# tracker.net
KiCad netlist of a schematic drawn in EAGLE
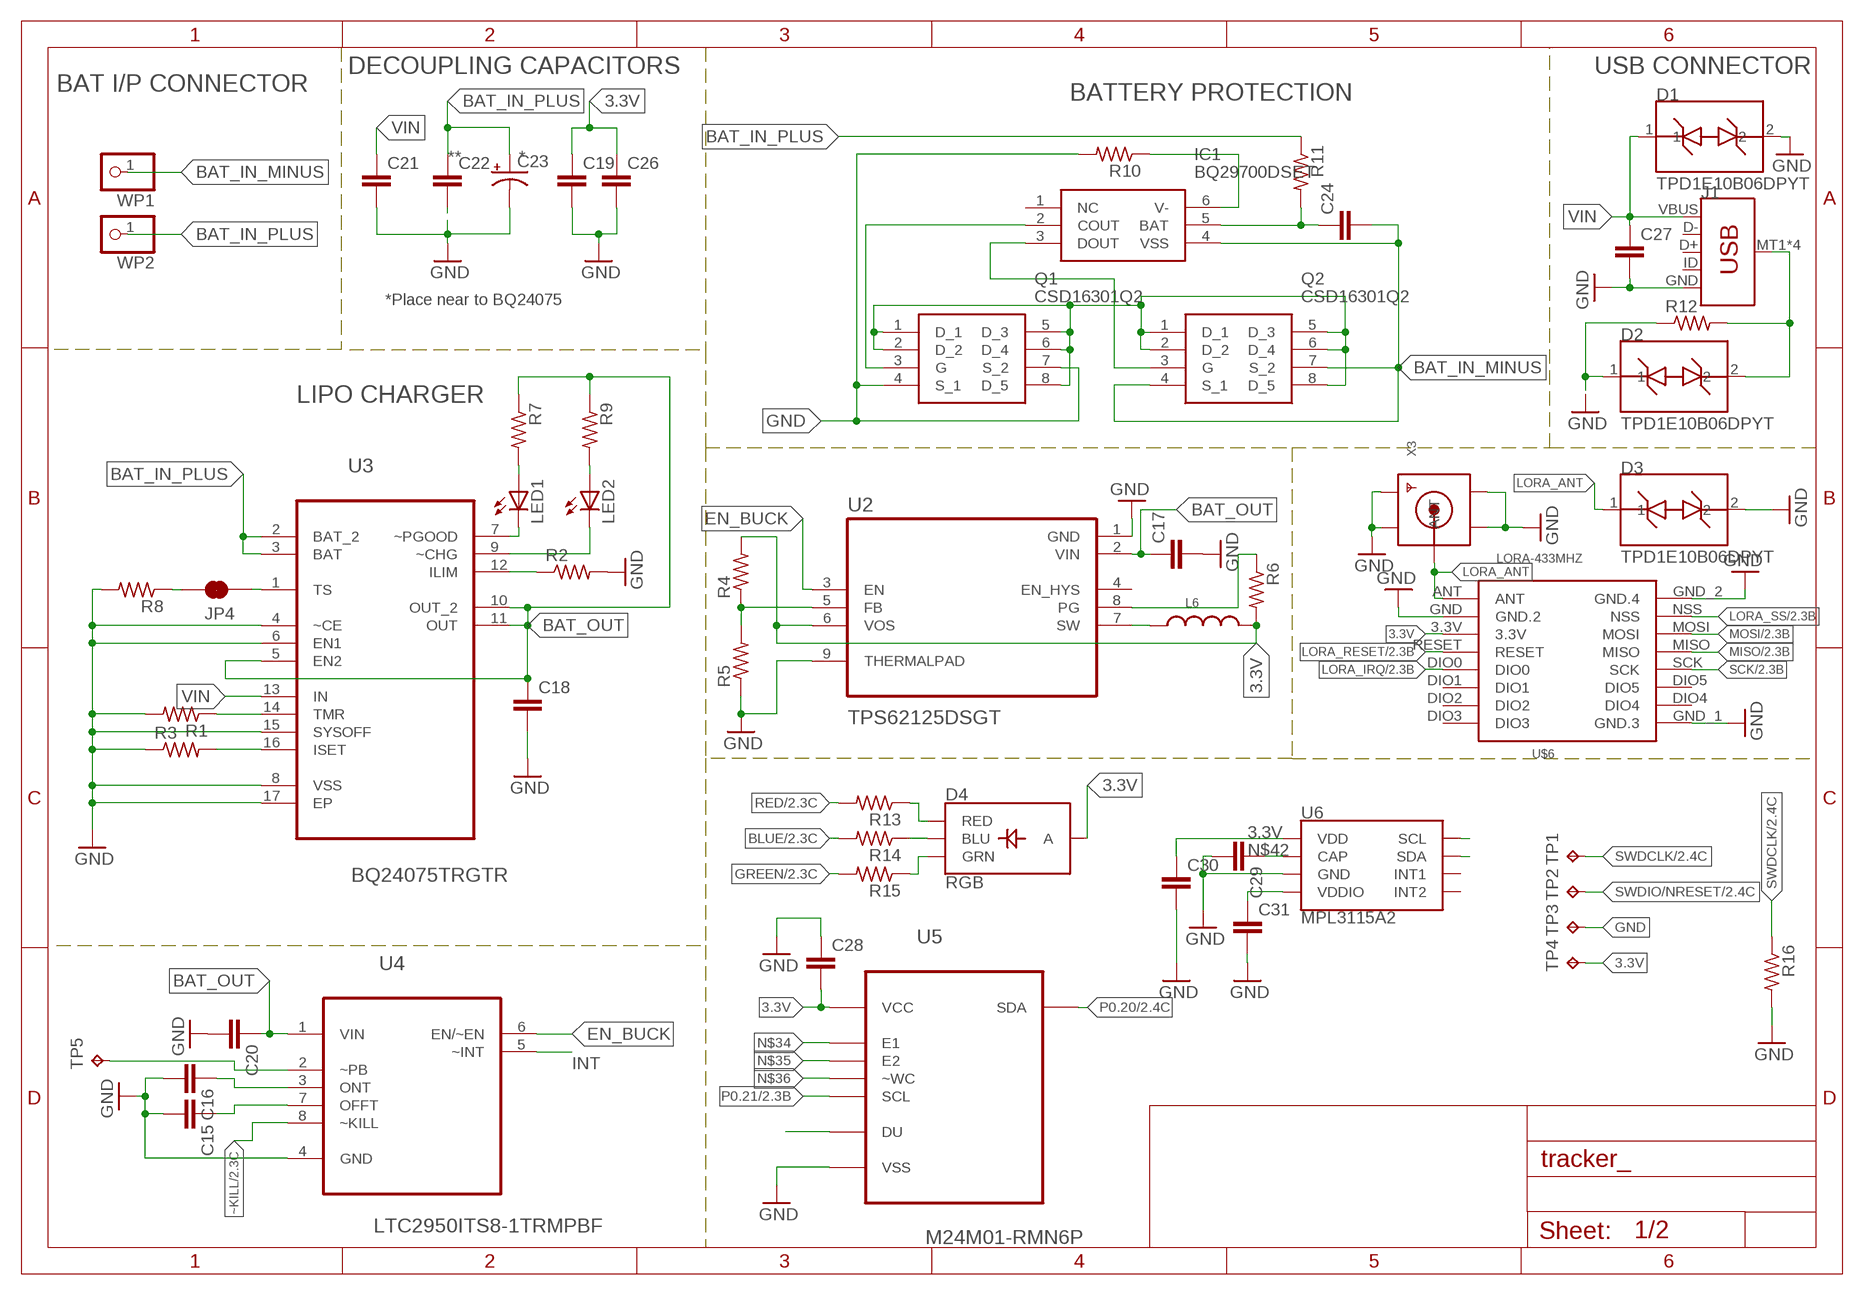
[diagram p0: schematic, sheet 1]
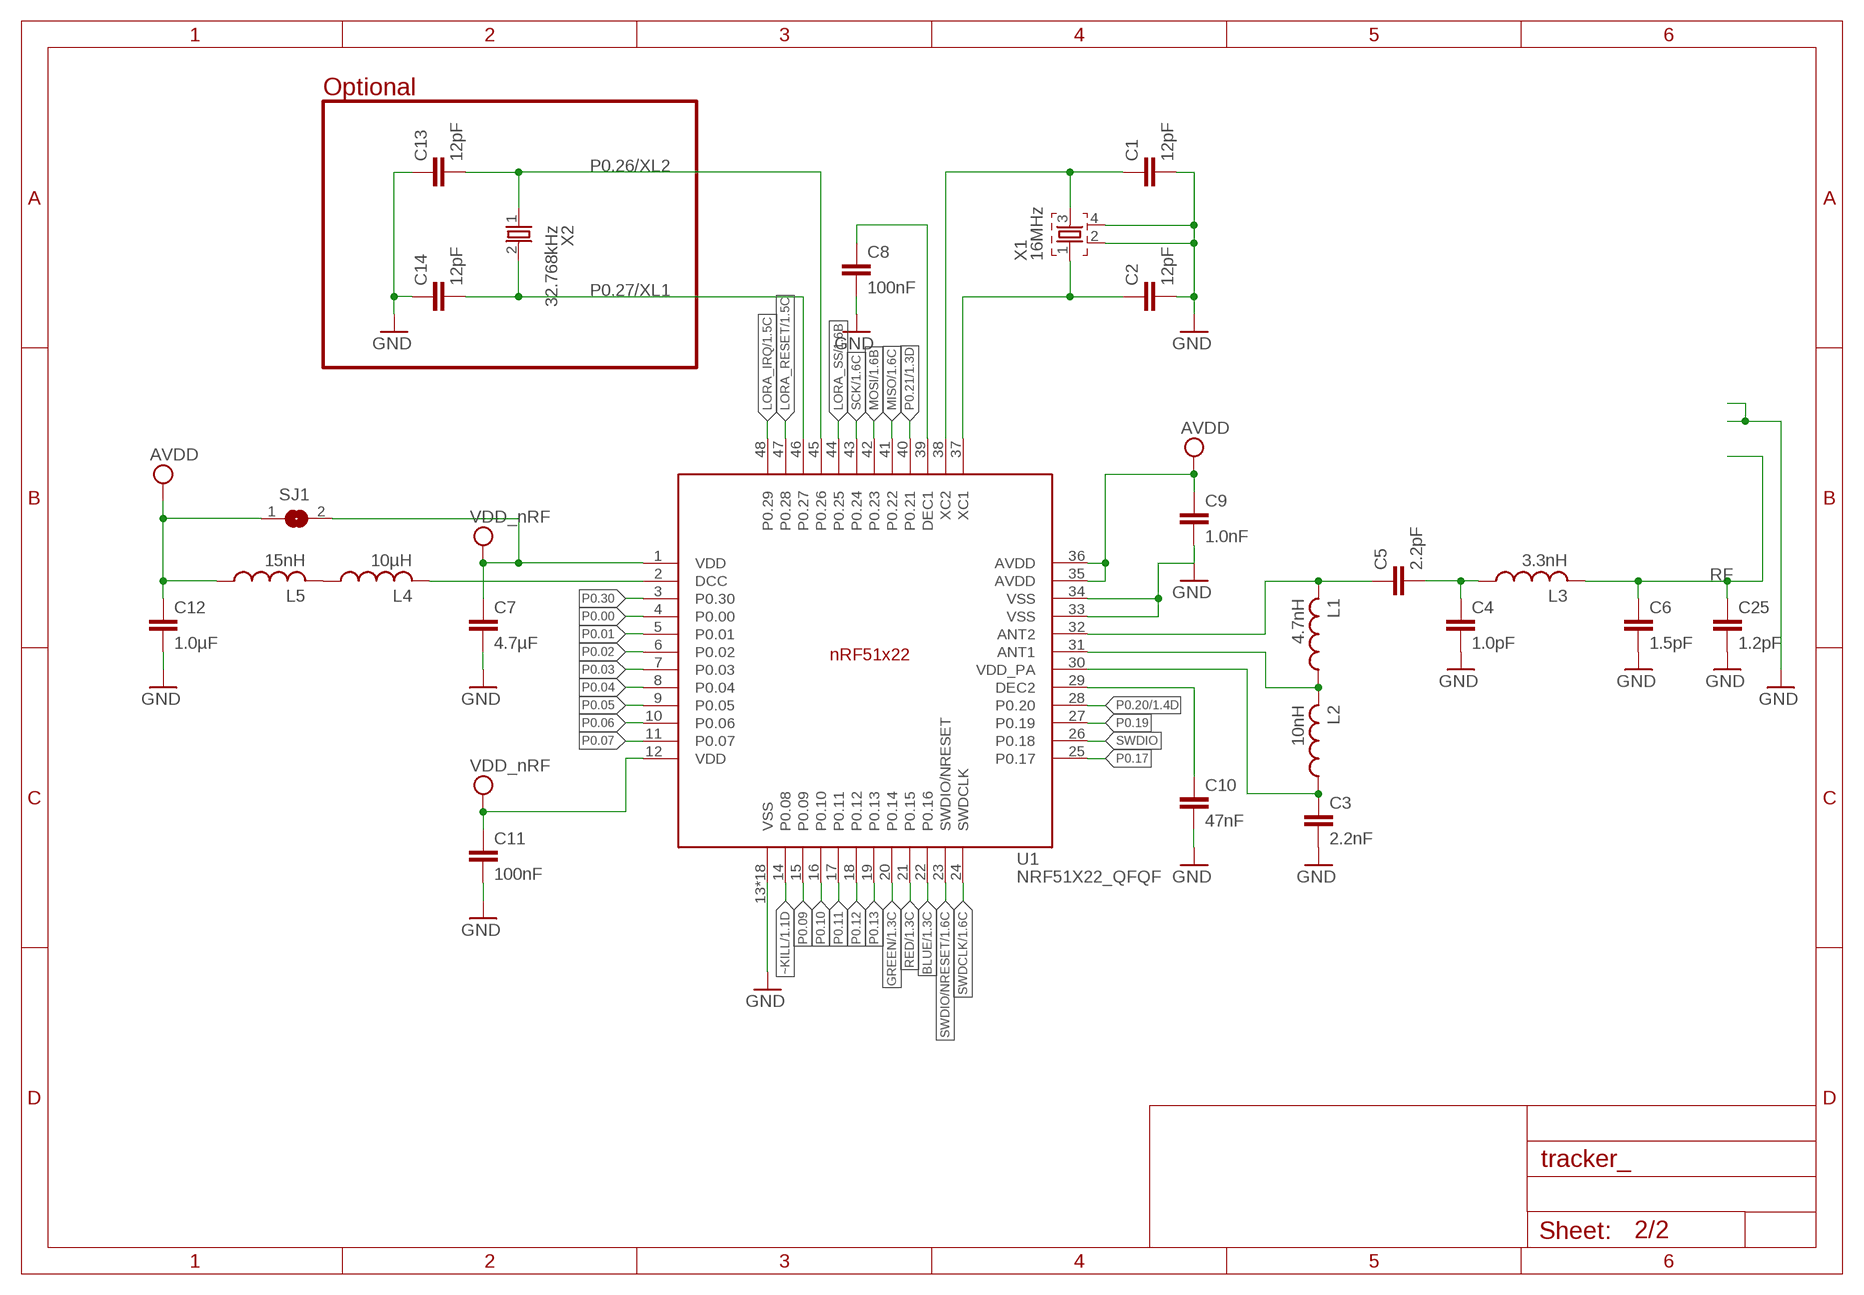
[diagram p1: schematic, sheet 2]

(export (version "E")
  (design (tool "Eeschema 10.0.6"))
  (components
    (comp (ref "C1")
      (value "12pF")
      (footprint "eagle-import:RESC0402_N")
      (libsource (lib "eagle-import") (part "CAPACITOR_0402_N"))
    )
    (comp (ref "C2")
      (value "12pF")
      (footprint "eagle-import:RESC0402_N")
      (libsource (lib "eagle-import") (part "CAPACITOR_0402_N"))
    )
    (comp (ref "C3")
      (value "2.2nF")
      (footprint "eagle-import:RESC0402_N")
      (libsource (lib "eagle-import") (part "CAPACITOR_0402_N"))
    )
    (comp (ref "C4")
      (value "1.0pF")
      (footprint "eagle-import:RESC0402_N")
      (libsource (lib "eagle-import") (part "CAPACITOR_0402_N"))
    )
    (comp (ref "C5")
      (value "2.2pF")
      (footprint "eagle-import:RESC0402_N")
      (libsource (lib "eagle-import") (part "CAPACITOR_0402_N"))
    )
    (comp (ref "C6")
      (value "1.5pF")
      (footprint "eagle-import:RESC0402_N")
      (libsource (lib "eagle-import") (part "CAPACITOR_0402_N"))
    )
    (comp (ref "C7")
      (value "4.7µF")
      (footprint "eagle-import:RESC0603_N")
      (libsource (lib "eagle-import") (part "CAPACITOR_0603_N"))
    )
    (comp (ref "C8")
      (value "100nF")
      (footprint "eagle-import:RESC0402_N")
      (libsource (lib "eagle-import") (part "CAPACITOR_0402_N"))
    )
    (comp (ref "C9")
      (value "1.0nF")
      (footprint "eagle-import:RESC0402_N")
      (libsource (lib "eagle-import") (part "CAPACITOR_0402_N"))
    )
    (comp (ref "C10")
      (value "47nF")
      (footprint "eagle-import:RESC0402_N")
      (libsource (lib "eagle-import") (part "CAPACITOR_0402_N"))
    )
    (comp (ref "C11")
      (value "100nF")
      (footprint "eagle-import:RESC0402_N")
      (libsource (lib "eagle-import") (part "CAPACITOR_0402_N"))
    )
    (comp (ref "C12")
      (value "1.0µF")
      (footprint "eagle-import:RESC0603_N")
      (libsource (lib "eagle-import") (part "CAPACITOR_0603_N"))
    )
    (comp (ref "C13")
      (value "12pF")
      (footprint "eagle-import:RESC0402_N")
      (libsource (lib "eagle-import") (part "CAPACITOR_0402_N"))
    )
    (comp (ref "C14")
      (value "12pF")
      (footprint "eagle-import:RESC0402_N")
      (libsource (lib "eagle-import") (part "CAPACITOR_0402_N"))
    )
    (comp (ref "C25")
      (value "1.2pF")
      (footprint "eagle-import:RESC0402_N")
      (libsource (lib "eagle-import") (part "CAPACITOR_0402_N"))
    )
    (comp (ref "L1")
      (value "4.7nH")
      (footprint "eagle-import:RESC0402_N")
      (libsource (lib "eagle-import") (part "INDUCTOR_0402_N"))
    )
    (comp (ref "L2")
      (value "10nH")
      (footprint "eagle-import:RESC0402_N")
      (libsource (lib "eagle-import") (part "INDUCTOR_0402_N"))
    )
    (comp (ref "L3")
      (value "3.3nH")
      (footprint "eagle-import:RESC0402_N")
      (libsource (lib "eagle-import") (part "INDUCTOR_0402_N"))
    )
    (comp (ref "L4")
      (value "10µH")
      (footprint "eagle-import:RESC0603_N")
      (libsource (lib "eagle-import") (part "INDUCTOR_0603_N"))
    )
    (comp (ref "L5")
      (value "15nH")
      (footprint "eagle-import:RESC0402_N")
      (libsource (lib "eagle-import") (part "INDUCTOR_0402_N"))
    )
    (comp (ref "SJ1") (value "SJ") (footprint "eagle-import:SJ") (libsource (lib "eagle-import") (part "SJ")))
    (comp (ref "U1")
      (value "NRF51X22_QFQF")
      (footprint "eagle-import:QFN40P600X600X90-48_N")
      (libsource (lib "eagle-import") (part "NRF51X22_QFQF"))
    )
    (comp (ref "X1")
      (value "16MHz")
      (footprint "eagle-import:BT-XTAL_2016_N")
      (libsource (lib "eagle-import") (part "XTAL_32MHZ"))
    )
    (comp (ref "X2")
      (value "32.768kHz")
      (footprint "eagle-import:XTAL_3215_N")
      (libsource (lib "eagle-import") (part "XTAL_32KHZ"))
    )
    (comp (ref "C15")
      (value "C-EUC0402")
      (footprint "eagle-import:C0402")
      (libsource (lib "eagle-import") (part "C-EUC0402"))
    )
    (comp (ref "C16")
      (value "C-EUC0402")
      (footprint "eagle-import:C0402")
      (libsource (lib "eagle-import") (part "C-EUC0402"))
    )
    (comp (ref "C17")
      (value "C-EUC0402")
      (footprint "eagle-import:C0402")
      (libsource (lib "eagle-import") (part "C-EUC0402"))
    )
    (comp (ref "C18")
      (value "C-EUC0402")
      (footprint "eagle-import:C0402")
      (libsource (lib "eagle-import") (part "C-EUC0402"))
    )
    (comp (ref "C19")
      (value "C-EUC0603")
      (footprint "eagle-import:C0603")
      (libsource (lib "eagle-import") (part "C-EUC0603"))
    )
    (comp (ref "C20")
      (value "C-EUC0402")
      (footprint "eagle-import:C0402")
      (libsource (lib "eagle-import") (part "C-EUC0402"))
    )
    (comp (ref "C21")
      (value "C-EUC0402")
      (footprint "eagle-import:C0402")
      (libsource (lib "eagle-import") (part "C-EUC0402"))
    )
    (comp (ref "C22")
      (value "C-EUC0805K")
      (footprint "eagle-import:C0805K")
      (libsource (lib "eagle-import") (part "C-EUC0805K"))
    )
    (comp (ref "C23")
      (value "CPOL-USB/3528-21W")
      (footprint "eagle-import:B_3528-21W")
      (libsource (lib "eagle-import") (part "CPOL-USB/3528-21W"))
    )
    (comp (ref "C24")
      (value "C-EUC0603")
      (footprint "eagle-import:C0603")
      (libsource (lib "eagle-import") (part "C-EUC0603"))
    )
    (comp (ref "C26")
      (value "C-EUC0603")
      (footprint "eagle-import:C0603")
      (libsource (lib "eagle-import") (part "C-EUC0603"))
    )
    (comp (ref "C27")
      (value "C-EUC0603")
      (footprint "eagle-import:C0603")
      (libsource (lib "eagle-import") (part "C-EUC0603"))
    )
    (comp (ref "C28")
      (value "C-EUC0402")
      (footprint "eagle-import:C0402")
      (libsource (lib "eagle-import") (part "C-EUC0402"))
    )
    (comp (ref "C29")
      (value "C-EUC0402")
      (footprint "eagle-import:C0402")
      (libsource (lib "eagle-import") (part "C-EUC0402"))
    )
    (comp (ref "C30")
      (value "C-EUC0402")
      (footprint "eagle-import:C0402")
      (libsource (lib "eagle-import") (part "C-EUC0402"))
    )
    (comp (ref "C31")
      (value "C-EUC0402")
      (footprint "eagle-import:C0402")
      (libsource (lib "eagle-import") (part "C-EUC0402"))
    )
    (comp (ref "D1")
      (value "TPD1E10B06DPYT")
      (footprint "eagle-import:DFN100X60X45-2N")
      (fields (field (name "MF") "Texas Instruments"))
      (libsource (lib "eagle-import") (part "TPD1E10B06DPYT"))
    )
    (comp (ref "D2")
      (value "TPD1E10B06DPYT")
      (footprint "eagle-import:DFN100X60X45-2N")
      (fields (field (name "MF") "Texas Instruments"))
      (libsource (lib "eagle-import") (part "TPD1E10B06DPYT"))
    )
    (comp (ref "D3")
      (value "TPD1E10B06DPYT")
      (footprint "eagle-import:DFN100X60X45-2N")
      (fields (field (name "MF") "Texas Instruments"))
      (libsource (lib "eagle-import") (part "TPD1E10B06DPYT"))
    )
    (comp (ref "D4")
      (value "RGB")
      (footprint "eagle-import:P-LCC-4-3")
      (libsource (lib "eagle-import") (part "LED-RGB-CAPLCC"))
    )
    (comp (ref "IC1")
      (value "BQ29700DSET")
      (footprint "eagle-import:SON50P150X150X80-6N")
      (fields (field (name "RS_PART_NUMBER") "1456841"))
      (libsource (lib "eagle-import") (part "BQ29700DSET"))
    )
    (comp (ref "J1")
      (value "USB_MICRO-B_SMT")
      (footprint "eagle-import:USB-MICROB")
      (libsource (lib "eagle-import") (part "USB_MICRO-B_SMT"))
    )
    (comp (ref "JP4")
      (value "JUMPER-SMT_2_NC_TRACE_SILK")
      (footprint "eagle-import:SMT-JUMPER_2_NC_TRACE_SILK")
      (libsource (lib "eagle-import") (part "JUMPER-SMT_2_NC_TRACE_SILK"))
    )
    (comp (ref "L6")
      (value "WE-GF_1210(M)_744764115")
      (footprint "eagle-import:WE-GF_1210")
      (libsource (lib "eagle-import") (part "WE-GF_1210(M)_744764115"))
    )
    (comp (ref "LED1")
      (value "LEDCHIPLED_0603")
      (footprint "eagle-import:CHIPLED_0603")
      (libsource (lib "eagle-import") (part "LEDCHIPLED_0603"))
    )
    (comp (ref "LED2")
      (value "LEDCHIPLED_0603")
      (footprint "eagle-import:CHIPLED_0603")
      (libsource (lib "eagle-import") (part "LEDCHIPLED_0603"))
    )
    (comp (ref "Q1")
      (value "CSD16301Q2")
      (footprint "eagle-import:CSD16301Q2")
      (fields (field (name "RS_PART_NUMBER") "1628525"))
      (libsource (lib "eagle-import") (part "CSD16301Q2"))
    )
    (comp (ref "Q2")
      (value "CSD16301Q2")
      (footprint "eagle-import:CSD16301Q2")
      (fields (field (name "RS_PART_NUMBER") "1628525"))
      (libsource (lib "eagle-import") (part "CSD16301Q2"))
    )
    (comp (ref "R1")
      (value "R-US_R0402")
      (footprint "eagle-import:R0402")
      (libsource (lib "eagle-import") (part "R-US_R0402"))
    )
    (comp (ref "R2")
      (value "R-US_R0402")
      (footprint "eagle-import:R0402")
      (libsource (lib "eagle-import") (part "R-US_R0402"))
    )
    (comp (ref "R3")
      (value "R-US_R0402")
      (footprint "eagle-import:R0402")
      (libsource (lib "eagle-import") (part "R-US_R0402"))
    )
    (comp (ref "R4")
      (value "R-US_R0402")
      (footprint "eagle-import:R0402")
      (libsource (lib "eagle-import") (part "R-US_R0402"))
    )
    (comp (ref "R5")
      (value "R-US_R0402")
      (footprint "eagle-import:R0402")
      (libsource (lib "eagle-import") (part "R-US_R0402"))
    )
    (comp (ref "R6")
      (value "R-US_R0402")
      (footprint "eagle-import:R0402")
      (libsource (lib "eagle-import") (part "R-US_R0402"))
    )
    (comp (ref "R7")
      (value "R-US_R0402")
      (footprint "eagle-import:R0402")
      (libsource (lib "eagle-import") (part "R-US_R0402"))
    )
    (comp (ref "R8")
      (value "R-US_R0402")
      (footprint "eagle-import:R0402")
      (libsource (lib "eagle-import") (part "R-US_R0402"))
    )
    (comp (ref "R9")
      (value "R-US_R0402")
      (footprint "eagle-import:R0402")
      (libsource (lib "eagle-import") (part "R-US_R0402"))
    )
    (comp (ref "R10")
      (value "R-US_R0402")
      (footprint "eagle-import:R0402")
      (libsource (lib "eagle-import") (part "R-US_R0402"))
    )
    (comp (ref "R11")
      (value "R-US_M0805")
      (footprint "eagle-import:M0805")
      (libsource (lib "eagle-import") (part "R-US_M0805"))
    )
    (comp (ref "R12")
      (value "R-US_R0402")
      (footprint "eagle-import:R0402")
      (libsource (lib "eagle-import") (part "R-US_R0402"))
    )
    (comp (ref "R13")
      (value "R-US_R0402")
      (footprint "eagle-import:R0402")
      (libsource (lib "eagle-import") (part "R-US_R0402"))
    )
    (comp (ref "R14")
      (value "R-US_R0402")
      (footprint "eagle-import:R0402")
      (libsource (lib "eagle-import") (part "R-US_R0402"))
    )
    (comp (ref "R15")
      (value "R-US_R0402")
      (footprint "eagle-import:R0402")
      (libsource (lib "eagle-import") (part "R-US_R0402"))
    )
    (comp (ref "R16")
      (value "R-US_R0402")
      (footprint "eagle-import:R0402")
      (libsource (lib "eagle-import") (part "R-US_R0402"))
    )
    (comp (ref "TP1")
      (value "TPB1,27")
      (footprint "eagle-import:B1,27")
      (libsource (lib "eagle-import") (part "TPB1,27"))
    )
    (comp (ref "TP2")
      (value "TPB1,27")
      (footprint "eagle-import:B1,27")
      (libsource (lib "eagle-import") (part "TPB1,27"))
    )
    (comp (ref "TP3")
      (value "TPB1,27")
      (footprint "eagle-import:B1,27")
      (libsource (lib "eagle-import") (part "TPB1,27"))
    )
    (comp (ref "TP4")
      (value "TPB1,27")
      (footprint "eagle-import:B1,27")
      (libsource (lib "eagle-import") (part "TPB1,27"))
    )
    (comp (ref "TP5")
      (value "TPB1,27")
      (footprint "eagle-import:B1,27")
      (libsource (lib "eagle-import") (part "TPB1,27"))
    )
    (comp (ref "U$6")
      (value "LORA-433MHZ")
      (footprint "eagle-import:LORA-RA1-SMD")
      (libsource (lib "eagle-import") (part "LORA-RA-01-433MHZ"))
    )
    (comp (ref "U2")
      (value "TPS62125DSGT")
      (footprint "eagle-import:SON50P200X200X80-9N")
      (fields (field (name "MF") "Texas Instruments"))
      (libsource (lib "eagle-import") (part "TPS62125DSGT"))
    )
    (comp (ref "U3")
      (value "BQ24075TRGTR")
      (footprint "eagle-import:QFN50P300X300X100-17N")
      (libsource (lib "eagle-import") (part "BQ24075TRGTR"))
    )
    (comp (ref "U4")
      (value "LTC2950ITS8-1TRMPBF")
      (footprint "eagle-import:SOT65P280X100-8N")
      (fields (field (name "MPN") "LTC2950ITS8-1#TRMPBF"))
      (libsource (lib "eagle-import") (part "LTC2950ITS8-1TRMPBF"))
    )
    (comp (ref "U5")
      (value "M24M01-RMN6P")
      (footprint "eagle-import:SOIC127P600X175-8N")
      (libsource (lib "eagle-import") (part "M24M01-RMN6P"))
    )
    (comp (ref "U6")
      (value "MPL3115A2")
      (footprint "eagle-import:LGA-8-5X3")
      (libsource (lib "eagle-import") (part "MPL3115A2"))
    )
    (comp (ref "WP1")
      (value "WPAD-1-0805")
      (footprint "eagle-import:WPAD-1-0805")
      (libsource (lib "eagle-import") (part "WPAD-1-0805"))
    )
    (comp (ref "WP2")
      (value "WPAD-1-0805")
      (footprint "eagle-import:WPAD-1-0805")
      (libsource (lib "eagle-import") (part "WPAD-1-0805"))
    )
    (comp (ref "X3")
      (value "SMACONNECTOR_EDGE")
      (footprint "eagle-import:SMA_EDGELAUNCH")
      (libsource (lib "eagle-import") (part "SMACONNECTOR_EDGE"))
    )
  )
  (nets
    (net (code "1") (name "3.3V") (class "Default")
      (node (ref "C11") (pin "1") (pinfunction "1_1") (pintype "passive"))
      (node (ref "C19") (pin "1") (pinfunction "1_1") (pintype "passive"))
      (node (ref "C26") (pin "1") (pinfunction "1_1") (pintype "passive"))
      (node (ref "C28") (pin "2") (pinfunction "2_2") (pintype "passive"))
      (node (ref "C30") (pin "1") (pinfunction "1_1") (pintype "passive"))
      (node (ref "C7") (pin "1") (pinfunction "1_1") (pintype "passive"))
      (node (ref "D4") (pin "4") (pinfunction "A_4") (pintype "bidirectional"))
      (node (ref "L6") (pin "2") (pinfunction "2_2") (pintype "passive"))
      (node (ref "R4") (pin "2") (pinfunction "2_2") (pintype "passive"))
      (node (ref "R6") (pin "2") (pinfunction "2_2") (pintype "passive"))
      (node (ref "SJ1") (pin "2") (pinfunction "2_2") (pintype "passive"))
      (node (ref "TP4") (pin "TP") (pinfunction "TP_TP") (pintype "input"))
      (node (ref "U$6") (pin "3.3V") (pinfunction "3.3V_3.3V") (pintype "power_in"))
      (node (ref "U1") (pin "1") (pinfunction "VDD_1") (pintype "power_in"))
      (node (ref "U1") (pin "12") (pinfunction "VDD_12") (pintype "power_in"))
      (node (ref "U2") (pin "6") (pinfunction "VOS_6") (pintype "input"))
      (node (ref "U5") (pin "8") (pinfunction "VCC_8") (pintype "power_in"))
      (node (ref "U6") (pin "1") (pinfunction "VDD_1") (pintype "power_in"))
    )
    (net (code "2") (name "AVDD") (class "Default")
      (node (ref "C12") (pin "1") (pinfunction "1_1") (pintype "passive"))
      (node (ref "C9") (pin "1") (pinfunction "1_1") (pintype "passive"))
      (node (ref "L5") (pin "1") (pinfunction "1_1") (pintype "passive"))
      (node (ref "SJ1") (pin "1") (pinfunction "1_1") (pintype "passive"))
      (node (ref "U1") (pin "35") (pinfunction "AVDD_35") (pintype "power_in"))
      (node (ref "U1") (pin "36") (pinfunction "AVDD_36") (pintype "power_in"))
    )
    (net (code "3") (name "BAT_IN_MINUS") (class "Default")
      (node (ref "C24") (pin "2") (pinfunction "2_2") (pintype "passive"))
      (node (ref "IC1") (pin "4") (pinfunction "VSS_4") (pintype "power_in"))
      (node (ref "Q2") (pin "4") (pinfunction "S_1_4") (pintype "bidirectional"))
      (node (ref "Q2") (pin "7") (pinfunction "S_2_7") (pintype "bidirectional"))
      (node (ref "WP1") (pin "1") (pinfunction "1_1") (pintype "passive"))
    )
    (net (code "4") (name "BAT_IN_PLUS") (class "Default")
      (node (ref "C22") (pin "1") (pinfunction "1_1") (pintype "passive"))
      (node (ref "C23") (pin "+") (pinfunction "+_+") (pintype "passive"))
      (node (ref "R11") (pin "1") (pinfunction "1_1") (pintype "passive"))
      (node (ref "U3") (pin "2") (pinfunction "BAT_2_2") (pintype "bidirectional"))
      (node (ref "U3") (pin "3") (pinfunction "BAT_3") (pintype "bidirectional"))
      (node (ref "WP2") (pin "1") (pinfunction "1_1") (pintype "passive"))
    )
    (net (code "5") (name "BAT_OUT") (class "Default")
      (node (ref "C17") (pin "1") (pinfunction "1_1") (pintype "passive"))
      (node (ref "C18") (pin "1") (pinfunction "1_1") (pintype "passive"))
      (node (ref "C20") (pin "1") (pinfunction "1_1") (pintype "passive"))
      (node (ref "R7") (pin "1") (pinfunction "1_1") (pintype "passive"))
      (node (ref "R9") (pin "1") (pinfunction "1_1") (pintype "passive"))
      (node (ref "U2") (pin "2") (pinfunction "VIN_2") (pintype "power_in"))
      (node (ref "U3") (pin "10") (pinfunction "OUT_2_10") (pintype "output"))
      (node (ref "U3") (pin "11") (pinfunction "OUT_11") (pintype "output"))
      (node (ref "U3") (pin "5") (pinfunction "EN2_5") (pintype "input"))
      (node (ref "U4") (pin "1") (pinfunction "VIN_1") (pintype "power_in"))
    )
    (net (code "6") (name "BLUE") (class "Default")
      (node (ref "R14") (pin "2") (pinfunction "2_2") (pintype "passive"))
      (node (ref "U1") (pin "22") (pinfunction "P0.16_22") (pintype "bidirectional"))
    )
    (net (code "7") (name "EN_BUCK") (class "Default")
      (node (ref "U2") (pin "3") (pinfunction "EN_3") (pintype "input"))
      (node (ref "U4") (pin "6") (pinfunction "EN/~{EN}_6") (pintype "output"))
    )
    (net (code "8") (name "GND") (class "Default")
      (node (ref "C1") (pin "2") (pinfunction "2_2") (pintype "passive"))
      (node (ref "C10") (pin "2") (pinfunction "2_2") (pintype "passive"))
      (node (ref "C11") (pin "2") (pinfunction "2_2") (pintype "passive"))
      (node (ref "C12") (pin "2") (pinfunction "2_2") (pintype "passive"))
      (node (ref "C13") (pin "1") (pinfunction "1_1") (pintype "passive"))
      (node (ref "C14") (pin "1") (pinfunction "1_1") (pintype "passive"))
      (node (ref "C15") (pin "2") (pinfunction "2_2") (pintype "passive"))
      (node (ref "C16") (pin "2") (pinfunction "2_2") (pintype "passive"))
      (node (ref "C17") (pin "2") (pinfunction "2_2") (pintype "passive"))
      (node (ref "C18") (pin "2") (pinfunction "2_2") (pintype "passive"))
      (node (ref "C19") (pin "2") (pinfunction "2_2") (pintype "passive"))
      (node (ref "C2") (pin "2") (pinfunction "2_2") (pintype "passive"))
      (node (ref "C20") (pin "2") (pinfunction "2_2") (pintype "passive"))
      (node (ref "C21") (pin "2") (pinfunction "2_2") (pintype "passive"))
      (node (ref "C22") (pin "2") (pinfunction "2_2") (pintype "passive"))
      (node (ref "C23") (pin "-") (pinfunction "-_-") (pintype "passive"))
      (node (ref "C25") (pin "2") (pinfunction "2_2") (pintype "passive"))
      (node (ref "C26") (pin "2") (pinfunction "2_2") (pintype "passive"))
      (node (ref "C27") (pin "2") (pinfunction "2_2") (pintype "passive"))
      (node (ref "C28") (pin "1") (pinfunction "1_1") (pintype "passive"))
      (node (ref "C29") (pin "2") (pinfunction "2_2") (pintype "passive"))
      (node (ref "C3") (pin "2") (pinfunction "2_2") (pintype "passive"))
      (node (ref "C30") (pin "2") (pinfunction "2_2") (pintype "passive"))
      (node (ref "C31") (pin "2") (pinfunction "2_2") (pintype "passive"))
      (node (ref "C4") (pin "2") (pinfunction "2_2") (pintype "passive"))
      (node (ref "C6") (pin "2") (pinfunction "2_2") (pintype "passive"))
      (node (ref "C7") (pin "2") (pinfunction "2_2") (pintype "passive"))
      (node (ref "C8") (pin "2") (pinfunction "2_2") (pintype "passive"))
      (node (ref "C9") (pin "2") (pinfunction "2_2") (pintype "passive"))
      (node (ref "D1") (pin "2") (pinfunction "2_2") (pintype "bidirectional"))
      (node (ref "D2") (pin "1") (pinfunction "1_1") (pintype "bidirectional"))
      (node (ref "D3") (pin "2") (pinfunction "2_2") (pintype "bidirectional"))
      (node (ref "J1") (pin "GND") (pinfunction "GND_GND") (pintype "power_in"))
      (node (ref "Q1") (pin "4") (pinfunction "S_1_4") (pintype "bidirectional"))
      (node (ref "Q1") (pin "7") (pinfunction "S_2_7") (pintype "bidirectional"))
      (node (ref "R1") (pin "2") (pinfunction "2_2") (pintype "passive"))
      (node (ref "R10") (pin "2") (pinfunction "2_2") (pintype "passive"))
      (node (ref "R12") (pin "1") (pinfunction "1_1") (pintype "passive"))
      (node (ref "R16") (pin "2") (pinfunction "2_2") (pintype "passive"))
      (node (ref "R2") (pin "2") (pinfunction "2_2") (pintype "passive"))
      (node (ref "R3") (pin "1") (pinfunction "1_1") (pintype "passive"))
      (node (ref "R5") (pin "1") (pinfunction "1_1") (pintype "passive"))
      (node (ref "R8") (pin "2") (pinfunction "2_2") (pintype "passive"))
      (node (ref "TP3") (pin "TP") (pinfunction "TP_TP") (pintype "input"))
      (node (ref "U$6") (pin "GND") (pinfunction "GND.2_GND") (pintype "power_in"))
      (node (ref "U$6") (pin "GND_1") (pinfunction "GND.3_GND_1") (pintype "power_in"))
      (node (ref "U$6") (pin "GND_2") (pinfunction "GND.4_GND_2") (pintype "power_in"))
      (node (ref "U1") (pin "13") (pinfunction "VSS_13") (pintype "power_in"))
      (node (ref "U1") (pin "33") (pinfunction "VSS_33") (pintype "power_in"))
      (node (ref "U1") (pin "34") (pinfunction "VSS_34") (pintype "power_in"))
      (node (ref "U1") (pin "PAD") (pinfunction "VSS_PAD") (pintype "power_in"))
      (node (ref "U1") (pin "PAD@VIA01") (pinfunction "VSS_PAD@VIA01") (pintype "power_in"))
      (node (ref "U1") (pin "PAD@VIA02") (pinfunction "VSS_PAD@VIA02") (pintype "power_in"))
      (node (ref "U1") (pin "PAD@VIA03") (pinfunction "VSS_PAD@VIA03") (pintype "power_in"))
      (node (ref "U1") (pin "PAD@VIA04") (pinfunction "VSS_PAD@VIA04") (pintype "power_in"))
      (node (ref "U1") (pin "PAD@VIA05") (pinfunction "VSS_PAD@VIA05") (pintype "power_in"))
      (node (ref "U1") (pin "PAD@VIA06") (pinfunction "VSS_PAD@VIA06") (pintype "power_in"))
      (node (ref "U1") (pin "PAD@VIA07") (pinfunction "VSS_PAD@VIA07") (pintype "power_in"))
      (node (ref "U1") (pin "PAD@VIA08") (pinfunction "VSS_PAD@VIA08") (pintype "power_in"))
      (node (ref "U1") (pin "PAD@VIA09") (pinfunction "VSS_PAD@VIA09") (pintype "power_in"))
      (node (ref "U1") (pin "PAD@VIA10") (pinfunction "VSS_PAD@VIA10") (pintype "power_in"))
      (node (ref "U1") (pin "PAD@VIA11") (pinfunction "VSS_PAD@VIA11") (pintype "power_in"))
      (node (ref "U1") (pin "PAD@VIA12") (pinfunction "VSS_PAD@VIA12") (pintype "power_in"))
      (node (ref "U1") (pin "PAD@VIA13") (pinfunction "VSS_PAD@VIA13") (pintype "power_in"))
      (node (ref "U1") (pin "PAD@VIA14") (pinfunction "VSS_PAD@VIA14") (pintype "power_in"))
      (node (ref "U1") (pin "PAD@VIA15") (pinfunction "VSS_PAD@VIA15") (pintype "power_in"))
      (node (ref "U1") (pin "PAD@VIA16") (pinfunction "VSS_PAD@VIA16") (pintype "power_in"))
      (node (ref "U2") (pin "1") (pinfunction "GND_1") (pintype "power_in"))
      (node (ref "U2") (pin "9") (pinfunction "THERMALPAD_9") (pintype "bidirectional"))
      (node (ref "U3") (pin "15") (pinfunction "SYSOFF_15") (pintype "input"))
      (node (ref "U3") (pin "17") (pinfunction "EP_17") (pintype "passive"))
      (node (ref "U3") (pin "4") (pinfunction "~{CE}_4") (pintype "input"))
      (node (ref "U3") (pin "6") (pinfunction "EN1_6") (pintype "input"))
      (node (ref "U3") (pin "8") (pinfunction "VSS_8") (pintype "passive"))
      (node (ref "U4") (pin "4") (pinfunction "GND_4") (pintype "passive"))
      (node (ref "U5") (pin "4") (pinfunction "VSS_4") (pintype "power_in"))
      (node (ref "U6") (pin "3") (pinfunction "GND_3") (pintype "power_in"))
      (node (ref "X1") (pin "2") (pinfunction "2_2") (pintype "passive"))
      (node (ref "X1") (pin "4") (pinfunction "4_4") (pintype "passive"))
      (node (ref "X3") (pin "GND@1") (pinfunction "GND4_GND@1") (pintype "power_in"))
      (node (ref "X3") (pin "GND@2") (pinfunction "GND3_GND@2") (pintype "power_in"))
      (node (ref "X3") (pin "GND@3") (pinfunction "GND2_GND@3") (pintype "power_in"))
      (node (ref "X3") (pin "GND@4") (pinfunction "GND1_GND@4") (pintype "power_in"))
    )
    (net (code "9") (name "GREEN") (class "Default")
      (node (ref "R15") (pin "2") (pinfunction "2_2") (pintype "passive"))
      (node (ref "U1") (pin "20") (pinfunction "P0.14_20") (pintype "bidirectional"))
    )
    (net (code "10") (name "INT") (class "Default")
      (node (ref "U4") (pin "5") (pinfunction "~{INT}_5") (pintype "output"))
    )
    (net (code "11") (name "LORA_ANT") (class "Default")
      (node (ref "D3") (pin "1") (pinfunction "1_1") (pintype "bidirectional"))
      (node (ref "U$6") (pin "ANT") (pinfunction "ANT_ANT") (pintype "power_in"))
      (node (ref "X3") (pin "P") (pinfunction "ANT_P") (pintype "bidirectional"))
    )
    (net (code "12") (name "LORA_IRQ") (class "Default")
      (node (ref "U$6") (pin "DIO0") (pinfunction "DIO0_DIO0") (pintype "bidirectional"))
      (node (ref "U1") (pin "48") (pinfunction "P0.29_48") (pintype "bidirectional"))
    )
    (net (code "13") (name "LORA_RESET") (class "Default")
      (node (ref "U$6") (pin "RESET") (pinfunction "RESET_RESET") (pintype "bidirectional"))
      (node (ref "U1") (pin "47") (pinfunction "P0.28_47") (pintype "bidirectional"))
    )
    (net (code "14") (name "LORA_SS") (class "Default")
      (node (ref "U$6") (pin "NSS") (pinfunction "NSS_NSS") (pintype "bidirectional"))
      (node (ref "U1") (pin "44") (pinfunction "P0.25_44") (pintype "bidirectional"))
    )
    (net (code "15") (name "MISO") (class "Default")
      (node (ref "U$6") (pin "MISO") (pinfunction "MISO_MISO") (pintype "bidirectional"))
      (node (ref "U1") (pin "41") (pinfunction "P0.22_41") (pintype "bidirectional"))
    )
    (net (code "16") (name "MOSI") (class "Default")
      (node (ref "U$6") (pin "MOSI") (pinfunction "MOSI_MOSI") (pintype "bidirectional"))
      (node (ref "U1") (pin "42") (pinfunction "P0.23_42") (pintype "bidirectional"))
    )
    (net (code "17") (name "N$34") (class "Default")
      (node (ref "U5") (pin "2") (pinfunction "E1_2") (pintype "input"))
    )
    (net (code "18") (name "N$35") (class "Default")
      (node (ref "U5") (pin "3") (pinfunction "E2_3") (pintype "input"))
    )
    (net (code "19") (name "N$36") (class "Default")
      (node (ref "U5") (pin "7") (pinfunction "~{WC}_7") (pintype "input"))
    )
    (net (code "20") (name "N$42") (class "Default")
      (node (ref "C29") (pin "1") (pinfunction "1_1") (pintype "passive"))
      (node (ref "U6") (pin "2") (pinfunction "CAP_2") (pintype "power_in"))
    )
    (net (code "21") (name "Net-(C4-Pad1)") (class "Default")
      (node (ref "C4") (pin "1") (pinfunction "1_1") (pintype "passive"))
      (node (ref "C5") (pin "2") (pinfunction "2_2") (pintype "passive"))
      (node (ref "L3") (pin "1") (pinfunction "1_1") (pintype "passive"))
    )
    (net (code "22") (name "Net-(D2-Pad2)") (class "Default")
      (node (ref "D2") (pin "2") (pinfunction "2_2") (pintype "bidirectional"))
      (node (ref "J1") (pin "MT1") (pinfunction "SHIELD_MT1") (pintype "bidirectional"))
      (node (ref "J1") (pin "MT2") (pinfunction "SHIELD_MT2") (pintype "bidirectional"))
      (node (ref "J1") (pin "P$1") (pinfunction "SHIELD_P$1") (pintype "bidirectional"))
      (node (ref "J1") (pin "P$2") (pinfunction "SHIELD_P$2") (pintype "bidirectional"))
      (node (ref "R12") (pin "2") (pinfunction "2_2") (pintype "passive"))
    )
    (net (code "23") (name "Net-(D4-BLU)") (class "Default")
      (node (ref "D4") (pin "3") (pinfunction "BLU_3") (pintype "bidirectional"))
      (node (ref "R14") (pin "1") (pinfunction "1_1") (pintype "passive"))
    )
    (net (code "24") (name "Net-(D4-GRN)") (class "Default")
      (node (ref "D4") (pin "2") (pinfunction "GRN_2") (pintype "bidirectional"))
      (node (ref "R15") (pin "1") (pinfunction "1_1") (pintype "passive"))
    )
    (net (code "25") (name "Net-(D4-RED)") (class "Default")
      (node (ref "D4") (pin "1") (pinfunction "RED_1") (pintype "bidirectional"))
      (node (ref "R13") (pin "1") (pinfunction "1_1") (pintype "passive"))
    )
    (net (code "26") (name "Net-(IC1-BAT)") (class "Default")
      (node (ref "C24") (pin "1") (pinfunction "1_1") (pintype "passive"))
      (node (ref "IC1") (pin "5") (pinfunction "BAT_5") (pintype "power_in"))
      (node (ref "R11") (pin "2") (pinfunction "2_2") (pintype "passive"))
    )
    (net (code "27") (name "Net-(IC1-COUT)") (class "Default")
      (node (ref "IC1") (pin "2") (pinfunction "COUT_2") (pintype "output"))
      (node (ref "Q1") (pin "3") (pinfunction "G_3") (pintype "bidirectional"))
    )
    (net (code "28") (name "Net-(IC1-DOUT)") (class "Default")
      (node (ref "IC1") (pin "3") (pinfunction "DOUT_3") (pintype "output"))
      (node (ref "Q2") (pin "3") (pinfunction "G_3") (pintype "bidirectional"))
    )
    (net (code "29") (name "Net-(IC1-V-)") (class "Default")
      (node (ref "IC1") (pin "6") (pinfunction "V-_6") (pintype "power_in"))
      (node (ref "R10") (pin "1") (pinfunction "1_1") (pintype "passive"))
    )
    (net (code "30") (name "Net-(JP4-Pad2)") (class "Default")
      (node (ref "JP4") (pin "2") (pinfunction "2_2") (pintype "passive"))
      (node (ref "R8") (pin "1") (pinfunction "1_1") (pintype "passive"))
    )
    (net (code "31") (name "Net-(L4-Pad1)") (class "Default")
      (node (ref "L4") (pin "1") (pinfunction "1_1") (pintype "passive"))
      (node (ref "L5") (pin "2") (pinfunction "2_2") (pintype "passive"))
    )
    (net (code "32") (name "Net-(LED1-PadA)") (class "Default")
      (node (ref "LED1") (pin "A") (pinfunction "A_A") (pintype "passive"))
      (node (ref "R7") (pin "2") (pinfunction "2_2") (pintype "passive"))
    )
    (net (code "33") (name "Net-(LED2-PadA)") (class "Default")
      (node (ref "LED2") (pin "A") (pinfunction "A_A") (pintype "passive"))
      (node (ref "R9") (pin "2") (pinfunction "2_2") (pintype "passive"))
    )
    (net (code "34") (name "Net-(Q1-D_1)") (class "Default")
      (node (ref "Q1") (pin "1") (pinfunction "D_1_1") (pintype "bidirectional"))
      (node (ref "Q1") (pin "2") (pinfunction "D_2_2") (pintype "bidirectional"))
      (node (ref "Q1") (pin "5") (pinfunction "D_3_5") (pintype "bidirectional"))
      (node (ref "Q1") (pin "6") (pinfunction "D_4_6") (pintype "bidirectional"))
      (node (ref "Q1") (pin "8") (pinfunction "D_5_8") (pintype "bidirectional"))
      (node (ref "Q2") (pin "1") (pinfunction "D_1_1") (pintype "bidirectional"))
      (node (ref "Q2") (pin "2") (pinfunction "D_2_2") (pintype "bidirectional"))
      (node (ref "Q2") (pin "5") (pinfunction "D_3_5") (pintype "bidirectional"))
      (node (ref "Q2") (pin "6") (pinfunction "D_4_6") (pintype "bidirectional"))
      (node (ref "Q2") (pin "8") (pinfunction "D_5_8") (pintype "bidirectional"))
    )
    (net (code "35") (name "Net-(U1-ANT1)") (class "Default")
      (node (ref "L1") (pin "1") (pinfunction "1_1") (pintype "passive"))
      (node (ref "L2") (pin "2") (pinfunction "2_2") (pintype "passive"))
      (node (ref "U1") (pin "31") (pinfunction "ANT1_31") (pintype "bidirectional"))
    )
    (net (code "36") (name "Net-(U1-ANT2)") (class "Default")
      (node (ref "C5") (pin "1") (pinfunction "1_1") (pintype "passive"))
      (node (ref "L1") (pin "2") (pinfunction "2_2") (pintype "passive"))
      (node (ref "U1") (pin "32") (pinfunction "ANT2_32") (pintype "bidirectional"))
    )
    (net (code "37") (name "Net-(U1-DCC)") (class "Default")
      (node (ref "L4") (pin "2") (pinfunction "2_2") (pintype "passive"))
      (node (ref "U1") (pin "2") (pinfunction "DCC_2") (pintype "power_in"))
    )
    (net (code "38") (name "Net-(U1-DEC1)") (class "Default")
      (node (ref "C8") (pin "1") (pinfunction "1_1") (pintype "passive"))
      (node (ref "U1") (pin "39") (pinfunction "DEC1_39") (pintype "power_in"))
    )
    (net (code "39") (name "Net-(U1-DEC2)") (class "Default")
      (node (ref "C10") (pin "1") (pinfunction "1_1") (pintype "passive"))
      (node (ref "U1") (pin "29") (pinfunction "DEC2_29") (pintype "power_in"))
    )
    (net (code "40") (name "Net-(U1-VDD_PA)") (class "Default")
      (node (ref "C3") (pin "1") (pinfunction "1_1") (pintype "passive"))
      (node (ref "L2") (pin "1") (pinfunction "1_1") (pintype "passive"))
      (node (ref "U1") (pin "30") (pinfunction "VDD_PA_30") (pintype "power_in"))
    )
    (net (code "41") (name "Net-(U1-XC1)") (class "Default")
      (node (ref "C2") (pin "1") (pinfunction "1_1") (pintype "passive"))
      (node (ref "U1") (pin "37") (pinfunction "XC1_37") (pintype "bidirectional"))
      (node (ref "X1") (pin "1") (pinfunction "1_1") (pintype "passive"))
    )
    (net (code "42") (name "Net-(U1-XC2)") (class "Default")
      (node (ref "C1") (pin "1") (pinfunction "1_1") (pintype "passive"))
      (node (ref "U1") (pin "38") (pinfunction "XC2_38") (pintype "bidirectional"))
      (node (ref "X1") (pin "3") (pinfunction "3_3") (pintype "passive"))
    )
    (net (code "43") (name "Net-(U2-FB)") (class "Default")
      (node (ref "R4") (pin "1") (pinfunction "1_1") (pintype "passive"))
      (node (ref "R5") (pin "2") (pinfunction "2_2") (pintype "passive"))
      (node (ref "U2") (pin "5") (pinfunction "FB_5") (pintype "input"))
    )
    (net (code "44") (name "Net-(U2-PG)") (class "Default")
      (node (ref "R6") (pin "1") (pinfunction "1_1") (pintype "passive"))
      (node (ref "U2") (pin "8") (pinfunction "PG_8") (pintype "output"))
    )
    (net (code "45") (name "Net-(U2-SW)") (class "Default")
      (node (ref "L6") (pin "1") (pinfunction "1_1") (pintype "passive"))
      (node (ref "U2") (pin "7") (pinfunction "SW_7") (pintype "output"))
    )
    (net (code "46") (name "Net-(U3-ILIM)") (class "Default")
      (node (ref "R2") (pin "1") (pinfunction "1_1") (pintype "passive"))
      (node (ref "U3") (pin "12") (pinfunction "ILIM_12") (pintype "output"))
    )
    (net (code "47") (name "Net-(U3-ISET)") (class "Default")
      (node (ref "R3") (pin "2") (pinfunction "2_2") (pintype "passive"))
      (node (ref "U3") (pin "16") (pinfunction "ISET_16") (pintype "bidirectional"))
    )
    (net (code "48") (name "Net-(U3-TMR)") (class "Default")
      (node (ref "R1") (pin "1") (pinfunction "1_1") (pintype "passive"))
      (node (ref "U3") (pin "14") (pinfunction "TMR_14") (pintype "input"))
    )
    (net (code "49") (name "Net-(U3-TS)") (class "Default")
      (node (ref "JP4") (pin "1") (pinfunction "1_1") (pintype "passive"))
      (node (ref "U3") (pin "1") (pinfunction "TS_1") (pintype "bidirectional"))
    )
    (net (code "50") (name "Net-(U3-~{CHG})") (class "Default")
      (node (ref "LED2") (pin "C") (pinfunction "C_C") (pintype "passive"))
      (node (ref "U3") (pin "9") (pinfunction "~{CHG}_9") (pintype "output"))
    )
    (net (code "51") (name "Net-(U3-~{PGOOD})") (class "Default")
      (node (ref "LED1") (pin "C") (pinfunction "C_C") (pintype "passive"))
      (node (ref "U3") (pin "7") (pinfunction "~{PGOOD}_7") (pintype "output"))
    )
    (net (code "52") (name "Net-(U4-OFFT)") (class "Default")
      (node (ref "C15") (pin "1") (pinfunction "1_1") (pintype "passive"))
      (node (ref "U4") (pin "7") (pinfunction "OFFT_7") (pintype "input"))
    )
    (net (code "53") (name "Net-(U4-ONT)") (class "Default")
      (node (ref "C16") (pin "1") (pinfunction "1_1") (pintype "passive"))
      (node (ref "U4") (pin "3") (pinfunction "ONT_3") (pintype "input"))
    )
    (net (code "54") (name "Net-(U4-~{PB})") (class "Default")
      (node (ref "TP5") (pin "TP") (pinfunction "TP_TP") (pintype "input"))
      (node (ref "U4") (pin "2") (pinfunction "~{PB}_2") (pintype "input"))
    )
    (net (code "55") (name "Net-(U6-VDDIO)") (class "Default")
      (node (ref "C31") (pin "1") (pinfunction "1_1") (pintype "passive"))
      (node (ref "U6") (pin "4") (pinfunction "VDDIO_4") (pintype "power_in"))
    )
    (net (code "56") (name "P0.00") (class "Default")
      (node (ref "U1") (pin "4") (pinfunction "P0.00_4") (pintype "bidirectional"))
    )
    (net (code "57") (name "P0.01") (class "Default")
      (node (ref "U1") (pin "5") (pinfunction "P0.01_5") (pintype "bidirectional"))
    )
    (net (code "58") (name "P0.02") (class "Default")
      (node (ref "U1") (pin "6") (pinfunction "P0.02_6") (pintype "bidirectional"))
    )
    (net (code "59") (name "P0.03") (class "Default")
      (node (ref "U1") (pin "7") (pinfunction "P0.03_7") (pintype "bidirectional"))
    )
    (net (code "60") (name "P0.04") (class "Default")
      (node (ref "U1") (pin "8") (pinfunction "P0.04_8") (pintype "bidirectional"))
    )
    (net (code "61") (name "P0.05") (class "Default")
      (node (ref "U1") (pin "9") (pinfunction "P0.05_9") (pintype "bidirectional"))
    )
    (net (code "62") (name "P0.06") (class "Default")
      (node (ref "U1") (pin "10") (pinfunction "P0.06_10") (pintype "bidirectional"))
    )
    (net (code "63") (name "P0.07") (class "Default")
      (node (ref "U1") (pin "11") (pinfunction "P0.07_11") (pintype "bidirectional"))
    )
    (net (code "64") (name "P0.09") (class "Default")
      (node (ref "U1") (pin "15") (pinfunction "P0.09_15") (pintype "bidirectional"))
    )
    (net (code "65") (name "P0.10") (class "Default")
      (node (ref "U1") (pin "16") (pinfunction "P0.10_16") (pintype "bidirectional"))
    )
    (net (code "66") (name "P0.11") (class "Default")
      (node (ref "U1") (pin "17") (pinfunction "P0.11_17") (pintype "bidirectional"))
    )
    (net (code "67") (name "P0.12") (class "Default")
      (node (ref "U1") (pin "18") (pinfunction "P0.12_18") (pintype "bidirectional"))
    )
    (net (code "68") (name "P0.13") (class "Default")
      (node (ref "U1") (pin "19") (pinfunction "P0.13_19") (pintype "bidirectional"))
    )
    (net (code "69") (name "P0.17") (class "Default")
      (node (ref "U1") (pin "25") (pinfunction "P0.17_25") (pintype "bidirectional"))
    )
    (net (code "70") (name "P0.19") (class "Default")
      (node (ref "U1") (pin "27") (pinfunction "P0.19_27") (pintype "bidirectional"))
    )
    (net (code "71") (name "P0.20") (class "Default")
      (node (ref "U1") (pin "28") (pinfunction "P0.20_28") (pintype "bidirectional"))
      (node (ref "U5") (pin "5") (pinfunction "SDA_5") (pintype "output"))
      (node (ref "U6") (pin "7") (pinfunction "SDA_7") (pintype "bidirectional"))
    )
    (net (code "72") (name "P0.21") (class "Default")
      (node (ref "U1") (pin "40") (pinfunction "P0.21_40") (pintype "bidirectional"))
      (node (ref "U5") (pin "6") (pinfunction "SCL_6") (pintype "input"))
      (node (ref "U6") (pin "8") (pinfunction "SCL_8") (pintype "bidirectional"))
    )
    (net (code "73") (name "P0.26{slash}XL2") (class "Default")
      (node (ref "C13") (pin "2") (pinfunction "2_2") (pintype "passive"))
      (node (ref "U1") (pin "45") (pinfunction "P0.26_45") (pintype "bidirectional"))
      (node (ref "X2") (pin "1") (pinfunction "1_1") (pintype "passive"))
    )
    (net (code "74") (name "P0.27{slash}XL1") (class "Default")
      (node (ref "C14") (pin "2") (pinfunction "2_2") (pintype "passive"))
      (node (ref "U1") (pin "46") (pinfunction "P0.27_46") (pintype "bidirectional"))
      (node (ref "X2") (pin "2") (pinfunction "2_2") (pintype "passive"))
    )
    (net (code "75") (name "P0.30") (class "Default")
      (node (ref "U1") (pin "3") (pinfunction "P0.30_3") (pintype "bidirectional"))
    )
    (net (code "76") (name "RED") (class "Default")
      (node (ref "R13") (pin "2") (pinfunction "2_2") (pintype "passive"))
      (node (ref "U1") (pin "21") (pinfunction "P0.15_21") (pintype "bidirectional"))
    )
    (net (code "77") (name "RF") (class "Default")
      (node (ref "C25") (pin "1") (pinfunction "1_1") (pintype "passive"))
      (node (ref "C6") (pin "1") (pinfunction "1_1") (pintype "passive"))
      (node (ref "L3") (pin "2") (pinfunction "2_2") (pintype "passive"))
    )
    (net (code "78") (name "SCK") (class "Default")
      (node (ref "U$6") (pin "SCK") (pinfunction "SCK_SCK") (pintype "bidirectional"))
      (node (ref "U1") (pin "43") (pinfunction "P0.24_43") (pintype "bidirectional"))
    )
    (net (code "79") (name "SWDCLK") (class "Default")
      (node (ref "R16") (pin "1") (pinfunction "1_1") (pintype "passive"))
      (node (ref "TP1") (pin "TP") (pinfunction "TP_TP") (pintype "input"))
      (node (ref "U1") (pin "24") (pinfunction "SWDCLK_24") (pintype "input"))
    )
    (net (code "80") (name "SWDIO") (class "Default")
      (node (ref "U1") (pin "26") (pinfunction "P0.18_26") (pintype "bidirectional"))
    )
    (net (code "81") (name "SWDIO{slash}NRESET") (class "Default")
      (node (ref "TP2") (pin "TP") (pinfunction "TP_TP") (pintype "input"))
      (node (ref "U1") (pin "23") (pinfunction "SWDIO/NRESET_23") (pintype "bidirectional"))
    )
    (net (code "82") (name "VIN") (class "Default")
      (node (ref "C21") (pin "1") (pinfunction "1_1") (pintype "passive"))
      (node (ref "C27") (pin "1") (pinfunction "1_1") (pintype "passive"))
      (node (ref "D1") (pin "1") (pinfunction "1_1") (pintype "bidirectional"))
      (node (ref "J1") (pin "VBUS") (pinfunction "VBUS_VBUS") (pintype "power_in"))
      (node (ref "U3") (pin "13") (pinfunction "IN_13") (pintype "input"))
    )
    (net (code "83") (name "unconnected-(IC1-NC-Pad1)") (class "Default")
      (node (ref "IC1") (pin "1") (pinfunction "NC_1") (pintype "no_connect"))
    )
    (net (code "84") (name "unconnected-(J1-PadD+)") (class "Default")
      (node (ref "J1") (pin "D+") (pinfunction "D+_D+") (pintype "bidirectional"))
    )
    (net (code "85") (name "unconnected-(J1-PadD-)") (class "Default")
      (node (ref "J1") (pin "D-") (pinfunction "D-_D-") (pintype "bidirectional"))
    )
    (net (code "86") (name "unconnected-(J1-PadID)") (class "Default")
      (node (ref "J1") (pin "ID") (pinfunction "ID_ID") (pintype "bidirectional"))
    )
    (net (code "87") (name "unconnected-(U$6-PadDIO1)") (class "Default")
      (node (ref "U$6") (pin "DIO1") (pinfunction "DIO1_DIO1") (pintype "bidirectional"))
    )
    (net (code "88") (name "unconnected-(U$6-PadDIO2)") (class "Default")
      (node (ref "U$6") (pin "DIO2") (pinfunction "DIO2_DIO2") (pintype "bidirectional"))
    )
    (net (code "89") (name "unconnected-(U$6-PadDIO3)") (class "Default")
      (node (ref "U$6") (pin "DIO3") (pinfunction "DIO3_DIO3") (pintype "bidirectional"))
    )
    (net (code "90") (name "unconnected-(U$6-PadDIO4)") (class "Default")
      (node (ref "U$6") (pin "DIO4") (pinfunction "DIO4_DIO4") (pintype "bidirectional"))
    )
    (net (code "91") (name "unconnected-(U$6-PadDIO5)") (class "Default")
      (node (ref "U$6") (pin "DIO5") (pinfunction "DIO5_DIO5") (pintype "bidirectional"))
    )
    (net (code "92") (name "unconnected-(U2-EN_HYS-Pad4)") (class "Default")
      (node (ref "U2") (pin "4") (pinfunction "EN_HYS_4") (pintype "output"))
    )
    (net (code "93") (name "unconnected-(U5-DU-Pad1)") (class "Default")
      (node (ref "U5") (pin "1") (pinfunction "DU_1") (pintype "input"))
    )
    (net (code "94") (name "unconnected-(U6-INT1-Pad6)") (class "Default")
      (node (ref "U6") (pin "6") (pinfunction "INT1_6") (pintype "output"))
    )
    (net (code "95") (name "unconnected-(U6-INT2-Pad5)") (class "Default")
      (node (ref "U6") (pin "5") (pinfunction "INT2_5") (pintype "output"))
    )
    (net (code "96") (name "~{KILL}") (class "Default")
      (node (ref "U1") (pin "14") (pinfunction "P0.08_14") (pintype "bidirectional"))
      (node (ref "U4") (pin "8") (pinfunction "~{KILL}_8") (pintype "input"))
    )
  )
)
